# soic8.net
KiCad netlist of a schematic drawn in EAGLE
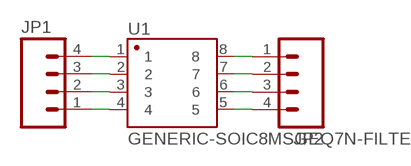
[diagram p0: schematic, sheet 1]

(export (version "E")
  (design (tool "Eeschema 10.0.6"))
  (components
    (comp (ref "JP1")
      (value "M04NO_SILK_ALL_ROUND")
      (footprint "eagle-import:1X04_NO_SILK_ALL_ROUND")
      (libsource (lib "eagle-import") (part "M04NO_SILK_ALL_ROUND"))
    )
    (comp (ref "JP2")
      (value "M04NO_SILK_ALL_ROUND")
      (footprint "eagle-import:1X04_NO_SILK_ALL_ROUND")
      (libsource (lib "eagle-import") (part "M04NO_SILK_ALL_ROUND"))
    )
    (comp (ref "U1")
      (value "GENERIC-SOIC8MSGEQ7N-FILTER")
      (footprint "eagle-import:SO08")
      (libsource (lib "eagle-import") (part "GENERIC-SOIC8MSGEQ7N-FILTER"))
    )
  )
  (nets
    (net (code "1") (name "Net-(JP1-Pad1)") (class "Default")
      (node (ref "JP1") (pin "1") (pinfunction "1_1") (pintype "passive"))
      (node (ref "U1") (pin "4") (pinfunction "4_4") (pintype "bidirectional"))
    )
    (net (code "2") (name "Net-(JP1-Pad2)") (class "Default")
      (node (ref "JP1") (pin "2") (pinfunction "2_2") (pintype "passive"))
      (node (ref "U1") (pin "3") (pinfunction "3_3") (pintype "bidirectional"))
    )
    (net (code "3") (name "Net-(JP1-Pad3)") (class "Default")
      (node (ref "JP1") (pin "3") (pinfunction "3_3") (pintype "passive"))
      (node (ref "U1") (pin "2") (pinfunction "2_2") (pintype "bidirectional"))
    )
    (net (code "4") (name "Net-(JP1-Pad4)") (class "Default")
      (node (ref "JP1") (pin "4") (pinfunction "4_4") (pintype "passive"))
      (node (ref "U1") (pin "1") (pinfunction "1_1") (pintype "bidirectional"))
    )
    (net (code "5") (name "Net-(JP2-Pad1)") (class "Default")
      (node (ref "JP2") (pin "1") (pinfunction "1_1") (pintype "passive"))
      (node (ref "U1") (pin "8") (pinfunction "8_8") (pintype "bidirectional"))
    )
    (net (code "6") (name "Net-(JP2-Pad2)") (class "Default")
      (node (ref "JP2") (pin "2") (pinfunction "2_2") (pintype "passive"))
      (node (ref "U1") (pin "7") (pinfunction "7_7") (pintype "bidirectional"))
    )
    (net (code "7") (name "Net-(JP2-Pad3)") (class "Default")
      (node (ref "JP2") (pin "3") (pinfunction "3_3") (pintype "passive"))
      (node (ref "U1") (pin "6") (pinfunction "6_6") (pintype "bidirectional"))
    )
    (net (code "8") (name "Net-(JP2-Pad4)") (class "Default")
      (node (ref "JP2") (pin "4") (pinfunction "4_4") (pintype "passive"))
      (node (ref "U1") (pin "5") (pinfunction "5_5") (pintype "bidirectional"))
    )
  )
)
